# microUSB.net
KiCad netlist of a schematic drawn in Altium Designer
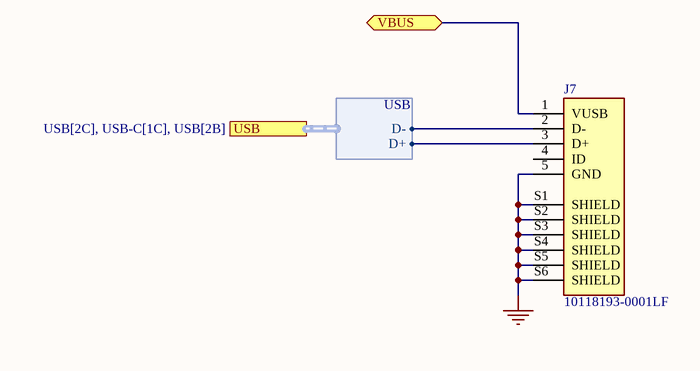
[diagram p0: microUSB.SchDoc]

(export (version "E")
  (design (tool "Eeschema 10.0.6"))
  (components
    (comp (ref "J7")
      (value "10118193-0001LF")
      (footprint "AMPHENOL_10118193-0001LF")
      (description "Micro USB 2.0, Input Output Connectors, B TYPE RECEPTACLE")
      (fields (field (name "MF") "Amphenol ICC"))
      (libsource (lib "Twill Technology Inc") (part "10118193-0001LF"))
    )
  )
  (nets
    (net (code "2") (name "/D+") (class "Default")
      (node (ref "J7") (pin "3") (pinfunction "D+_3") (pintype "passive"))
    )
    (net (code "3") (name "/D-") (class "Default")
      (node (ref "J7") (pin "2") (pinfunction "D-_2") (pintype "passive"))
    )
    (net (code "4") (name "/VBUS") (class "Default")
      (node (ref "J7") (pin "1") (pinfunction "VUSB_1") (pintype "passive"))
    )
    (net (code "6") (name "GND") (class "Default")
      (node (ref "J7") (pin "5") (pinfunction "GND_5") (pintype "passive"))
      (node (ref "J7") (pin "S1") (pinfunction "SHIELD_S1") (pintype "passive"))
      (node (ref "J7") (pin "S2") (pinfunction "SHIELD_S2") (pintype "passive"))
      (node (ref "J7") (pin "S3") (pinfunction "SHIELD_S3") (pintype "passive"))
      (node (ref "J7") (pin "S4") (pinfunction "SHIELD_S4") (pintype "passive"))
      (node (ref "J7") (pin "S5") (pinfunction "SHIELD_S5") (pintype "passive"))
      (node (ref "J7") (pin "S6") (pinfunction "SHIELD_S6") (pintype "passive"))
    )
    (net (code "7") (name "unconnected-(J7-ID-Pad4)") (class "Default")
      (node (ref "J7") (pin "4") (pinfunction "ID_4") (pintype "passive"))
    )
  )
)
